# midle_led.net
KiCad netlist of a schematic drawn in EAGLE
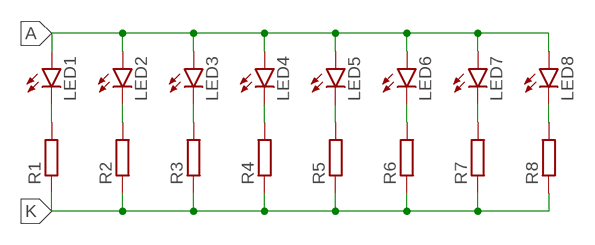
[diagram p0: schematic, sheet 1]

(export (version "E")
  (design (tool "Eeschema 10.0.6"))
  (components
    (comp (ref "LED1")
      (value "LED5MM")
      (footprint "eagle-import:LED5MM")
      (libsource (lib "eagle-import") (part "LED5MM"))
    )
    (comp (ref "LED2")
      (value "LED5MM")
      (footprint "eagle-import:LED5MM")
      (libsource (lib "eagle-import") (part "LED5MM"))
    )
    (comp (ref "LED3")
      (value "LED5MM")
      (footprint "eagle-import:LED5MM")
      (libsource (lib "eagle-import") (part "LED5MM"))
    )
    (comp (ref "LED4")
      (value "LED5MM")
      (footprint "eagle-import:LED5MM")
      (libsource (lib "eagle-import") (part "LED5MM"))
    )
    (comp (ref "LED5")
      (value "LED5MM")
      (footprint "eagle-import:LED5MM")
      (libsource (lib "eagle-import") (part "LED5MM"))
    )
    (comp (ref "LED6")
      (value "LED5MM")
      (footprint "eagle-import:LED5MM")
      (libsource (lib "eagle-import") (part "LED5MM"))
    )
    (comp (ref "LED7")
      (value "LED5MM")
      (footprint "eagle-import:LED5MM")
      (libsource (lib "eagle-import") (part "LED5MM"))
    )
    (comp (ref "LED8")
      (value "LED5MM")
      (footprint "eagle-import:LED5MM")
      (libsource (lib "eagle-import") (part "LED5MM"))
    )
    (comp (ref "R1")
      (value "R-EU_R0603")
      (footprint "eagle-import:R0603")
      (libsource (lib "eagle-import") (part "R-EU_R0603"))
    )
    (comp (ref "R2")
      (value "R-EU_R0603")
      (footprint "eagle-import:R0603")
      (libsource (lib "eagle-import") (part "R-EU_R0603"))
    )
    (comp (ref "R3")
      (value "R-EU_R0603")
      (footprint "eagle-import:R0603")
      (libsource (lib "eagle-import") (part "R-EU_R0603"))
    )
    (comp (ref "R4")
      (value "R-EU_R0603")
      (footprint "eagle-import:R0603")
      (libsource (lib "eagle-import") (part "R-EU_R0603"))
    )
    (comp (ref "R5")
      (value "R-EU_R0603")
      (footprint "eagle-import:R0603")
      (libsource (lib "eagle-import") (part "R-EU_R0603"))
    )
    (comp (ref "R6")
      (value "R-EU_R0603")
      (footprint "eagle-import:R0603")
      (libsource (lib "eagle-import") (part "R-EU_R0603"))
    )
    (comp (ref "R7")
      (value "R-EU_R0603")
      (footprint "eagle-import:R0603")
      (libsource (lib "eagle-import") (part "R-EU_R0603"))
    )
    (comp (ref "R8")
      (value "R-EU_R0603")
      (footprint "eagle-import:R0603")
      (libsource (lib "eagle-import") (part "R-EU_R0603"))
    )
  )
  (nets
    (net (code "1") (name "A") (class "Default")
      (node (ref "LED1") (pin "A") (pinfunction "A_A") (pintype "passive"))
      (node (ref "LED2") (pin "A") (pinfunction "A_A") (pintype "passive"))
      (node (ref "LED3") (pin "A") (pinfunction "A_A") (pintype "passive"))
      (node (ref "LED4") (pin "A") (pinfunction "A_A") (pintype "passive"))
      (node (ref "LED5") (pin "A") (pinfunction "A_A") (pintype "passive"))
      (node (ref "LED6") (pin "A") (pinfunction "A_A") (pintype "passive"))
      (node (ref "LED7") (pin "A") (pinfunction "A_A") (pintype "passive"))
      (node (ref "LED8") (pin "A") (pinfunction "A_A") (pintype "passive"))
    )
    (net (code "2") (name "K") (class "Default")
      (node (ref "R1") (pin "1") (pinfunction "1_1") (pintype "passive"))
      (node (ref "R2") (pin "1") (pinfunction "1_1") (pintype "passive"))
      (node (ref "R3") (pin "1") (pinfunction "1_1") (pintype "passive"))
      (node (ref "R4") (pin "1") (pinfunction "1_1") (pintype "passive"))
      (node (ref "R5") (pin "1") (pinfunction "1_1") (pintype "passive"))
      (node (ref "R6") (pin "1") (pinfunction "1_1") (pintype "passive"))
      (node (ref "R7") (pin "1") (pinfunction "1_1") (pintype "passive"))
      (node (ref "R8") (pin "1") (pinfunction "1_1") (pintype "passive"))
    )
    (net (code "3") (name "Net-(LED1-C)") (class "Default")
      (node (ref "LED1") (pin "K") (pinfunction "C_K") (pintype "passive"))
      (node (ref "R1") (pin "2") (pinfunction "2_2") (pintype "passive"))
    )
    (net (code "4") (name "Net-(LED2-C)") (class "Default")
      (node (ref "LED2") (pin "K") (pinfunction "C_K") (pintype "passive"))
      (node (ref "R2") (pin "2") (pinfunction "2_2") (pintype "passive"))
    )
    (net (code "5") (name "Net-(LED3-C)") (class "Default")
      (node (ref "LED3") (pin "K") (pinfunction "C_K") (pintype "passive"))
      (node (ref "R3") (pin "2") (pinfunction "2_2") (pintype "passive"))
    )
    (net (code "6") (name "Net-(LED4-C)") (class "Default")
      (node (ref "LED4") (pin "K") (pinfunction "C_K") (pintype "passive"))
      (node (ref "R4") (pin "2") (pinfunction "2_2") (pintype "passive"))
    )
    (net (code "7") (name "Net-(LED5-C)") (class "Default")
      (node (ref "LED5") (pin "K") (pinfunction "C_K") (pintype "passive"))
      (node (ref "R5") (pin "2") (pinfunction "2_2") (pintype "passive"))
    )
    (net (code "8") (name "Net-(LED6-C)") (class "Default")
      (node (ref "LED6") (pin "K") (pinfunction "C_K") (pintype "passive"))
      (node (ref "R6") (pin "2") (pinfunction "2_2") (pintype "passive"))
    )
    (net (code "9") (name "Net-(LED7-C)") (class "Default")
      (node (ref "LED7") (pin "K") (pinfunction "C_K") (pintype "passive"))
      (node (ref "R7") (pin "2") (pinfunction "2_2") (pintype "passive"))
    )
    (net (code "10") (name "Net-(LED8-C)") (class "Default")
      (node (ref "LED8") (pin "K") (pinfunction "C_K") (pintype "passive"))
      (node (ref "R8") (pin "2") (pinfunction "2_2") (pintype "passive"))
    )
  )
)
